# Peripherals.net
KiCad netlist of a schematic drawn in Altium Designer
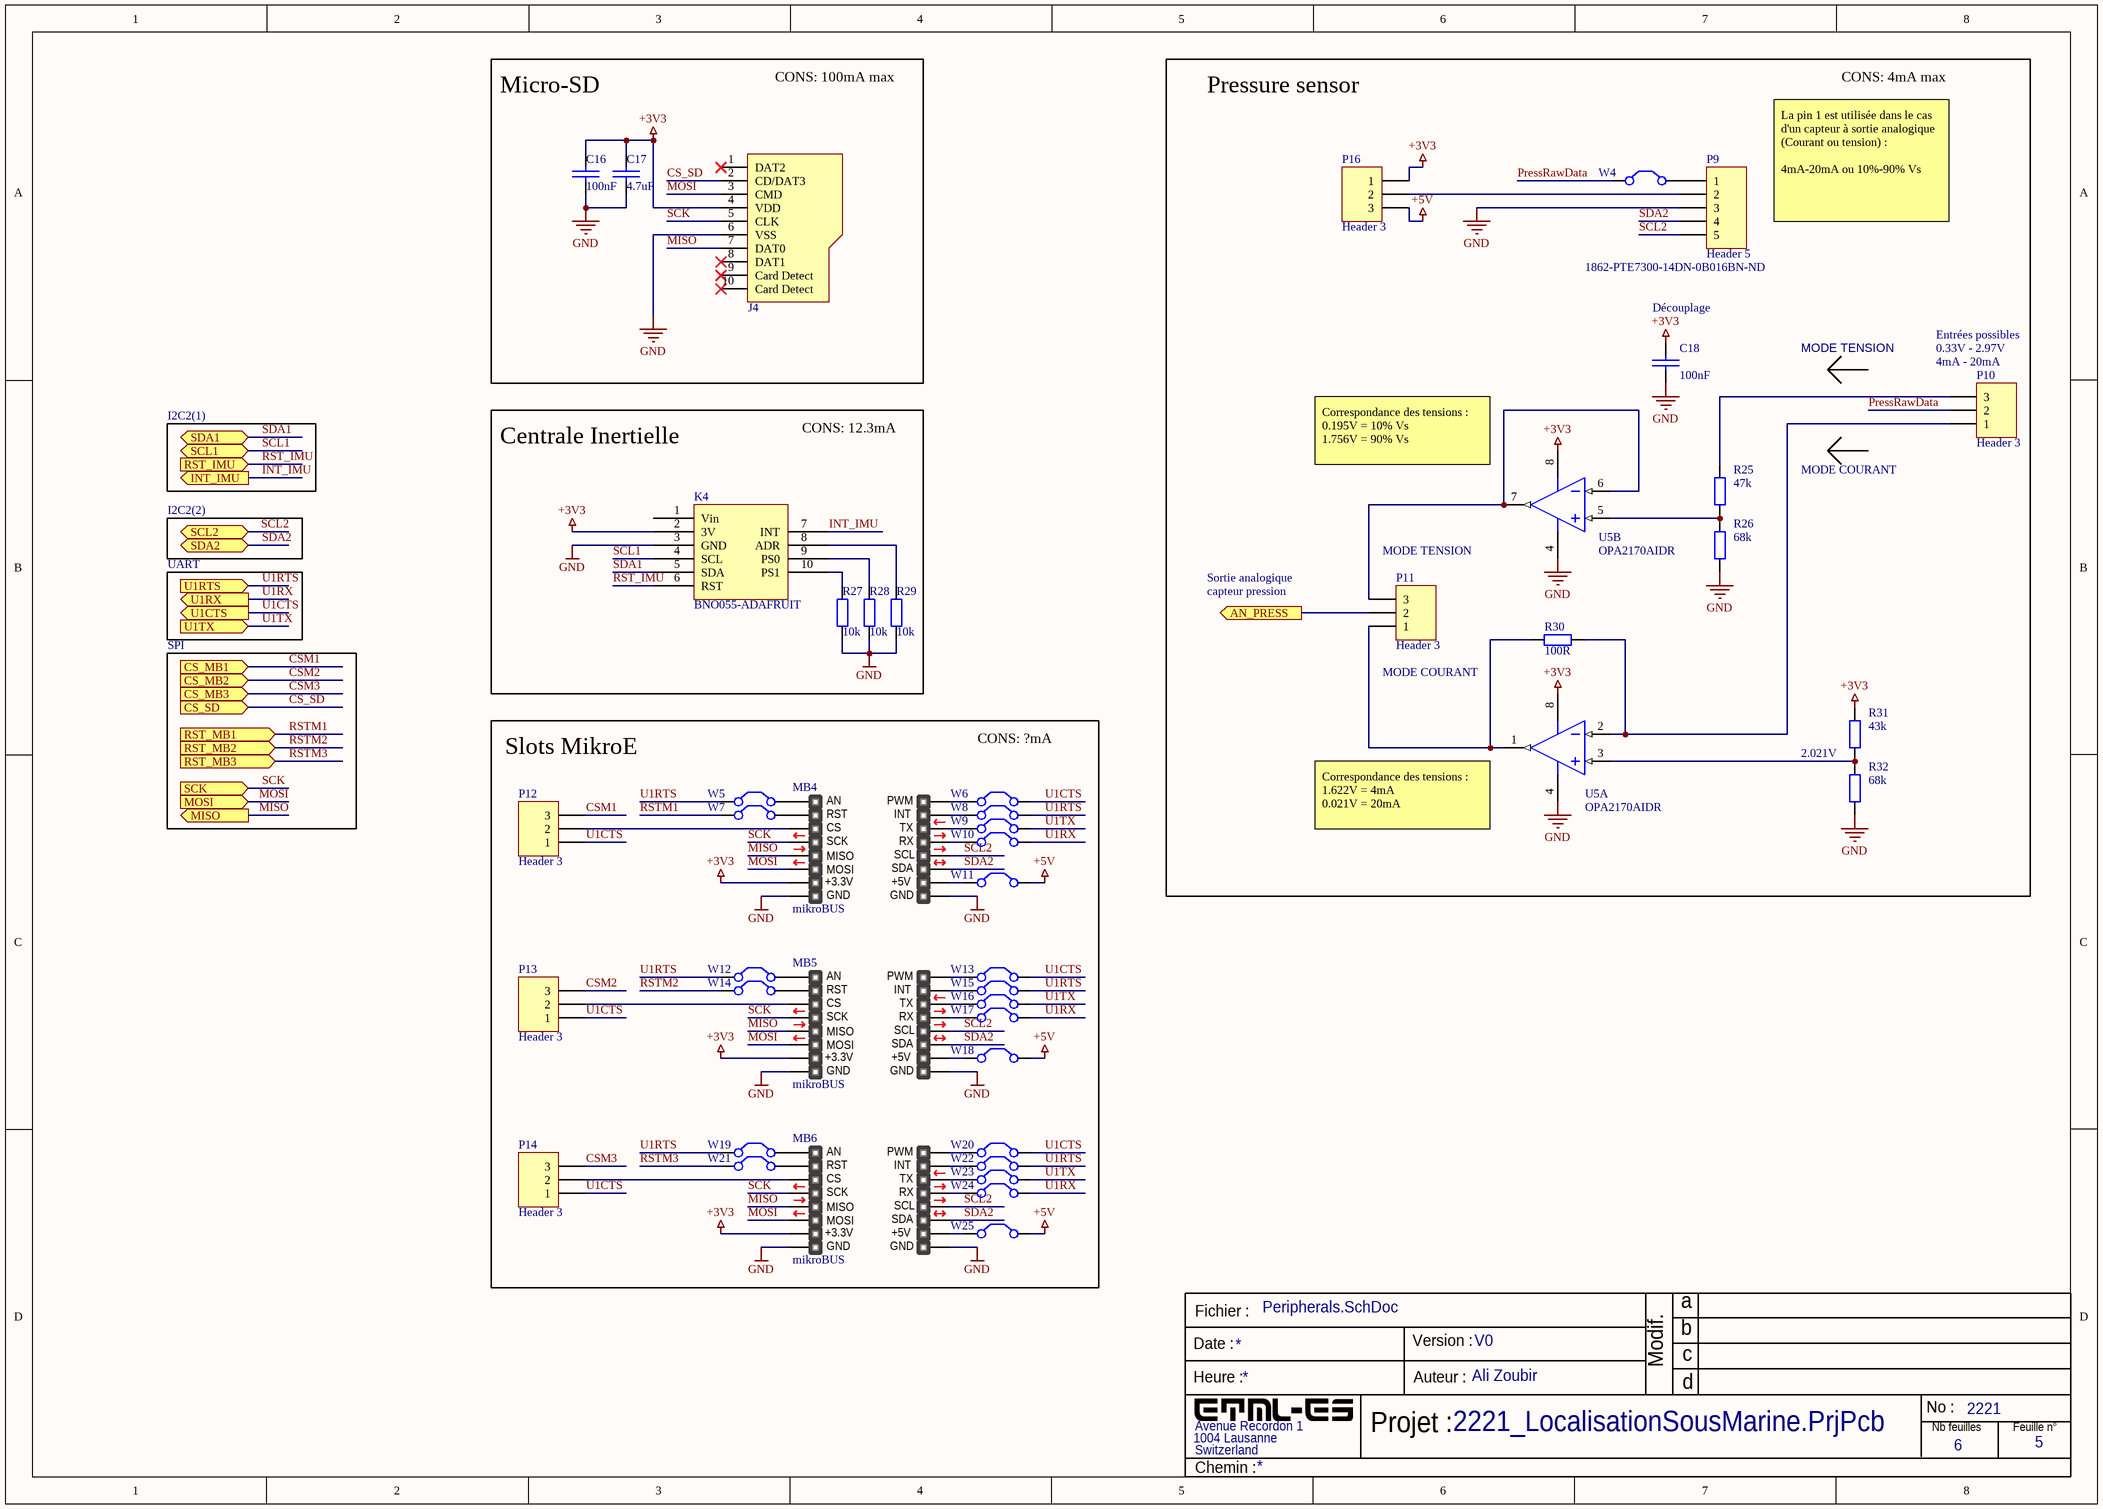
[diagram p0: Peripherals.SchDoc]

(export (version "E")
  (design (tool "Eeschema 10.0.6"))
  (components
    (comp (ref "C16") (value "100nF") (footprint "6-0805_L") (libsource (lib "*") (part "C")))
    (comp (ref "C17") (value "4.7uF") (footprint "6-0805_L") (libsource (lib "*") (part "C")))
    (comp (ref "C18") (value "100nF") (footprint "6-0805_L") (libsource (lib "*") (part "C")))
    (comp (ref "J4")
      (value "693071010811")
      (footprint "uSD-WE-693071010811")
      (description "WR-CRD Micro SD Card Connector Push & Push")
      (fields (field (name "MANUFACTURER") "Wurth Elektronik"))
      (libsource (lib "2221-LIB") (part "uSD-WE-693071010811"))
    )
    (comp (ref "K4")
      (value "BNO055-ADAFRUIT")
      (footprint "BNO055-ADAFRUIT")
      (libsource (lib "2221-LIB") (part "BNO055-ADAFRUIT"))
    )
    (comp (ref "MB4")
      (value "mikroBUS")
      (footprint "mikroBUS - Large")
      (description "mikroBUS compatible add-on board")
      (libsource (lib "mikroBUS_Add-on_standard") (part "mikroBUS compatible add-on board"))
    )
    (comp (ref "MB5")
      (value "mikroBUS")
      (footprint "mikroBUS - Large")
      (description "mikroBUS compatible add-on board")
      (libsource (lib "mikroBUS_Add-on_standard") (part "mikroBUS compatible add-on board"))
    )
    (comp (ref "MB6")
      (value "mikroBUS")
      (footprint "mikroBUS - Large")
      (description "mikroBUS compatible add-on board")
      (libsource (lib "mikroBUS_Add-on_standard") (part "mikroBUS compatible add-on board"))
    )
    (comp (ref "P9")
      (value "Header 5")
      (footprint "HDR1X5")
      (description "Header, 5-Pin")
      (fields
        (field (name "SUPPLIER PART NUMBER 1") "1862-PTE7300-14DN-0B016BN-ND")
        (field (name "PUBLISHER") "Altium Limited")
      )
      (libsource (lib "Miscellaneous Connectors") (part "Header 5"))
    )
    (comp (ref "P10")
      (value "Header 3")
      (footprint "HDR1X3")
      (description "Header, 3-Pin")
      (fields (field (name "PUBLISHER") "Altium Limited"))
      (libsource (lib "") (part "Header 3_2"))
    )
    (comp (ref "P11")
      (value "Header 3")
      (footprint "HDR1X3")
      (description "Header, 3-Pin")
      (fields (field (name "PUBLISHER") "Altium Limited"))
      (libsource (lib "") (part "Header 3_2"))
    )
    (comp (ref "P12")
      (value "Header 3")
      (footprint "HDR1X3")
      (description "Header, 3-Pin")
      (fields (field (name "PUBLISHER") "Altium Limited"))
      (libsource (lib "Miscellaneous Connectors") (part "Header 3"))
    )
    (comp (ref "P13")
      (value "Header 3")
      (footprint "HDR1X3")
      (description "Header, 3-Pin")
      (fields (field (name "PUBLISHER") "Altium Limited"))
      (libsource (lib "Miscellaneous Connectors") (part "Header 3"))
    )
    (comp (ref "P14")
      (value "Header 3")
      (footprint "HDR1X3")
      (description "Header, 3-Pin")
      (fields (field (name "PUBLISHER") "Altium Limited"))
      (libsource (lib "Miscellaneous Connectors") (part "Header 3"))
    )
    (comp (ref "P16")
      (value "Header 3")
      (footprint "HDR1X3")
      (description "Header, 3-Pin")
      (fields (field (name "PUBLISHER") "Altium Limited"))
      (libsource (lib "") (part "Header 3_1"))
    )
    (comp (ref "R25")
      (value "47k")
      (footprint "6-0805_L")
      (description "Res 0805")
      (fields (field (name "PUBLISHER") "Altium Limited"))
      (libsource (lib "Miscellaneous Devices") (part "Res2"))
    )
    (comp (ref "R26")
      (value "68k")
      (footprint "6-0805_L")
      (description "Res 0805")
      (fields (field (name "PUBLISHER") "Altium Limited"))
      (libsource (lib "Miscellaneous Devices") (part "Res2"))
    )
    (comp (ref "R27")
      (value "10k")
      (footprint "6-0805_L")
      (description "Res 0805")
      (fields (field (name "PUBLISHER") "Altium Limited"))
      (libsource (lib "Miscellaneous Devices") (part "Res2"))
    )
    (comp (ref "R28")
      (value "10k")
      (footprint "6-0805_L")
      (description "Res 0805")
      (fields (field (name "PUBLISHER") "Altium Limited"))
      (libsource (lib "Miscellaneous Devices") (part "Res2"))
    )
    (comp (ref "R29")
      (value "10k")
      (footprint "6-0805_L")
      (description "Res 0805")
      (fields (field (name "PUBLISHER") "Altium Limited"))
      (libsource (lib "Miscellaneous Devices") (part "Res2"))
    )
    (comp (ref "R30")
      (value "100R")
      (footprint "6-0805_L")
      (description "Res 0805")
      (fields (field (name "PUBLISHER") "Altium Limited"))
      (libsource (lib "") (part "Res2_1"))
    )
    (comp (ref "R31")
      (value "43k")
      (footprint "6-0805_L")
      (description "Res 0805")
      (fields (field (name "PUBLISHER") "Altium Limited"))
      (libsource (lib "Miscellaneous Devices") (part "Res2"))
    )
    (comp (ref "R32")
      (value "68k")
      (footprint "6-0805_L")
      (description "Res 0805")
      (fields (field (name "PUBLISHER") "Altium Limited"))
      (libsource (lib "Miscellaneous Devices") (part "Res2"))
    )
    (comp (ref "U5")
      (value "OPA2170AIDR")
      (footprint "D0008A_M")
      (fields (field (name "MANUFACTURER") "Texas Instruments"))
      (libsource (lib "Altium Content Vault") (part "TI-OPA-8_2"))
    )
    (comp (ref "W4")
      (value "Jumper")
      (footprint "JUMPER")
      (description "Jumper Wire")
      (fields (field (name "PUBLISHER") "Altium Limited"))
      (libsource (lib "Miscellaneous Devices") (part "Jumper"))
    )
    (comp (ref "W5")
      (value "Jumper")
      (footprint "JUMPER")
      (description "Jumper Wire")
      (fields (field (name "PUBLISHER") "Altium Limited"))
      (libsource (lib "Miscellaneous Devices") (part "Jumper"))
    )
    (comp (ref "W6")
      (value "Jumper")
      (footprint "JUMPER")
      (description "Jumper Wire")
      (fields (field (name "PUBLISHER") "Altium Limited"))
      (libsource (lib "Miscellaneous Devices") (part "Jumper"))
    )
    (comp (ref "W7")
      (value "Jumper")
      (footprint "JUMPER")
      (description "Jumper Wire")
      (fields (field (name "PUBLISHER") "Altium Limited"))
      (libsource (lib "Miscellaneous Devices") (part "Jumper"))
    )
    (comp (ref "W8")
      (value "Jumper")
      (footprint "JUMPER")
      (description "Jumper Wire")
      (fields (field (name "PUBLISHER") "Altium Limited"))
      (libsource (lib "Miscellaneous Devices") (part "Jumper"))
    )
    (comp (ref "W9")
      (value "Jumper")
      (footprint "JUMPER")
      (description "Jumper Wire")
      (fields (field (name "PUBLISHER") "Altium Limited"))
      (libsource (lib "Miscellaneous Devices") (part "Jumper"))
    )
    (comp (ref "W10")
      (value "Jumper")
      (footprint "JUMPER")
      (description "Jumper Wire")
      (fields (field (name "PUBLISHER") "Altium Limited"))
      (libsource (lib "Miscellaneous Devices") (part "Jumper"))
    )
    (comp (ref "W11")
      (value "Jumper")
      (footprint "JUMPER")
      (description "Jumper Wire")
      (fields (field (name "PUBLISHER") "Altium Limited"))
      (libsource (lib "Miscellaneous Devices") (part "Jumper"))
    )
    (comp (ref "W12")
      (value "Jumper")
      (footprint "JUMPER")
      (description "Jumper Wire")
      (fields (field (name "PUBLISHER") "Altium Limited"))
      (libsource (lib "Miscellaneous Devices") (part "Jumper"))
    )
    (comp (ref "W13")
      (value "Jumper")
      (footprint "JUMPER")
      (description "Jumper Wire")
      (fields (field (name "PUBLISHER") "Altium Limited"))
      (libsource (lib "Miscellaneous Devices") (part "Jumper"))
    )
    (comp (ref "W14")
      (value "Jumper")
      (footprint "JUMPER")
      (description "Jumper Wire")
      (fields (field (name "PUBLISHER") "Altium Limited"))
      (libsource (lib "Miscellaneous Devices") (part "Jumper"))
    )
    (comp (ref "W15")
      (value "Jumper")
      (footprint "JUMPER")
      (description "Jumper Wire")
      (fields (field (name "PUBLISHER") "Altium Limited"))
      (libsource (lib "Miscellaneous Devices") (part "Jumper"))
    )
    (comp (ref "W16")
      (value "Jumper")
      (footprint "JUMPER")
      (description "Jumper Wire")
      (fields (field (name "PUBLISHER") "Altium Limited"))
      (libsource (lib "Miscellaneous Devices") (part "Jumper"))
    )
    (comp (ref "W17")
      (value "Jumper")
      (footprint "JUMPER")
      (description "Jumper Wire")
      (fields (field (name "PUBLISHER") "Altium Limited"))
      (libsource (lib "Miscellaneous Devices") (part "Jumper"))
    )
    (comp (ref "W18")
      (value "Jumper")
      (footprint "JUMPER")
      (description "Jumper Wire")
      (fields (field (name "PUBLISHER") "Altium Limited"))
      (libsource (lib "Miscellaneous Devices") (part "Jumper"))
    )
    (comp (ref "W19")
      (value "Jumper")
      (footprint "JUMPER")
      (description "Jumper Wire")
      (fields (field (name "PUBLISHER") "Altium Limited"))
      (libsource (lib "Miscellaneous Devices") (part "Jumper"))
    )
    (comp (ref "W20")
      (value "Jumper")
      (footprint "JUMPER")
      (description "Jumper Wire")
      (fields (field (name "PUBLISHER") "Altium Limited"))
      (libsource (lib "Miscellaneous Devices") (part "Jumper"))
    )
    (comp (ref "W21")
      (value "Jumper")
      (footprint "JUMPER")
      (description "Jumper Wire")
      (fields (field (name "PUBLISHER") "Altium Limited"))
      (libsource (lib "Miscellaneous Devices") (part "Jumper"))
    )
    (comp (ref "W22")
      (value "Jumper")
      (footprint "JUMPER")
      (description "Jumper Wire")
      (fields (field (name "PUBLISHER") "Altium Limited"))
      (libsource (lib "Miscellaneous Devices") (part "Jumper"))
    )
    (comp (ref "W23")
      (value "Jumper")
      (footprint "JUMPER")
      (description "Jumper Wire")
      (fields (field (name "PUBLISHER") "Altium Limited"))
      (libsource (lib "Miscellaneous Devices") (part "Jumper"))
    )
    (comp (ref "W24")
      (value "Jumper")
      (footprint "JUMPER")
      (description "Jumper Wire")
      (fields (field (name "PUBLISHER") "Altium Limited"))
      (libsource (lib "Miscellaneous Devices") (part "Jumper"))
    )
    (comp (ref "W25")
      (value "Jumper")
      (footprint "JUMPER")
      (description "Jumper Wire")
      (fields (field (name "PUBLISHER") "Altium Limited"))
      (libsource (lib "Miscellaneous Devices") (part "Jumper"))
    )
  )
  (nets
    (net (code "1") (name "+3V3") (class "Default")
      (node (ref "C16") (pin "1") (pinfunction "1_1") (pintype "passive"))
      (node (ref "C17") (pin "1") (pinfunction "1_1") (pintype "passive"))
      (node (ref "C18") (pin "1") (pinfunction "1_1") (pintype "passive"))
      (node (ref "J4") (pin "4") (pinfunction "VDD_4") (pintype "passive"))
      (node (ref "K4") (pin "2") (pinfunction "3V_2") (pintype "passive"))
      (node (ref "MB4") (pin "7") (pinfunction "3.3V_7") (pintype "passive"))
      (node (ref "MB5") (pin "7") (pinfunction "3.3V_7") (pintype "passive"))
      (node (ref "MB6") (pin "7") (pinfunction "3.3V_7") (pintype "passive"))
      (node (ref "P16") (pin "1") (pinfunction "1_1") (pintype "passive"))
      (node (ref "R31") (pin "2") (pinfunction "2_2") (pintype "passive"))
      (node (ref "U5") (pin "8") (pinfunction "V+_8") (pintype "power_in"))
    )
    (net (code "2") (name "+5V") (class "Default")
      (node (ref "P16") (pin "3") (pinfunction "3_3") (pintype "passive"))
      (node (ref "W11") (pin "2") (pinfunction "C2_2") (pintype "passive"))
      (node (ref "W18") (pin "2") (pinfunction "C2_2") (pintype "passive"))
      (node (ref "W25") (pin "2") (pinfunction "C2_2") (pintype "passive"))
    )
    (net (code "3") (name "/AN_PRESS") (class "Default")
      (node (ref "P11") (pin "2") (pinfunction "2_2") (pintype "passive"))
    )
    (net (code "4") (name "/CSM1") (class "Default")
      (node (ref "P12") (pin "3") (pinfunction "3_3") (pintype "passive"))
    )
    (net (code "5") (name "/CSM2") (class "Default")
      (node (ref "P13") (pin "3") (pinfunction "3_3") (pintype "passive"))
    )
    (net (code "6") (name "/CSM3") (class "Default")
      (node (ref "P14") (pin "3") (pinfunction "3_3") (pintype "passive"))
    )
    (net (code "7") (name "/CS_SD") (class "Default")
      (node (ref "J4") (pin "2") (pinfunction "CD/DAT3_2") (pintype "passive"))
    )
    (net (code "8") (name "/INT_IMU") (class "Default")
      (node (ref "K4") (pin "7") (pinfunction "INT_7") (pintype "passive"))
    )
    (net (code "9") (name "/MISO") (class "Default")
      (node (ref "J4") (pin "7") (pinfunction "DAT0_7") (pintype "passive"))
      (node (ref "MB4") (pin "5") (pinfunction "MISO_5") (pintype "passive"))
      (node (ref "MB5") (pin "5") (pinfunction "MISO_5") (pintype "passive"))
      (node (ref "MB6") (pin "5") (pinfunction "MISO_5") (pintype "passive"))
    )
    (net (code "10") (name "/MOSI") (class "Default")
      (node (ref "J4") (pin "3") (pinfunction "CMD_3") (pintype "passive"))
      (node (ref "MB4") (pin "6") (pinfunction "MOSI_6") (pintype "passive"))
      (node (ref "MB5") (pin "6") (pinfunction "MOSI_6") (pintype "passive"))
      (node (ref "MB6") (pin "6") (pinfunction "MOSI_6") (pintype "passive"))
    )
    (net (code "11") (name "/PressRawData") (class "Default")
      (node (ref "P10") (pin "2") (pinfunction "2_2") (pintype "passive"))
      (node (ref "W4") (pin "1") (pinfunction "C1_1") (pintype "passive"))
    )
    (net (code "12") (name "/RSTM1") (class "Default")
      (node (ref "W7") (pin "1") (pinfunction "C1_1") (pintype "passive"))
    )
    (net (code "13") (name "/RSTM2") (class "Default")
      (node (ref "W14") (pin "1") (pinfunction "C1_1") (pintype "passive"))
    )
    (net (code "14") (name "/RSTM3") (class "Default")
      (node (ref "W21") (pin "1") (pinfunction "C1_1") (pintype "passive"))
    )
    (net (code "15") (name "/RST_IMU") (class "Default")
      (node (ref "K4") (pin "6") (pinfunction "RST_6") (pintype "passive"))
    )
    (net (code "16") (name "/SCK") (class "Default")
      (node (ref "J4") (pin "5") (pinfunction "CLK_5") (pintype "passive"))
      (node (ref "MB4") (pin "4") (pinfunction "SCK_4") (pintype "passive"))
      (node (ref "MB5") (pin "4") (pinfunction "SCK_4") (pintype "passive"))
      (node (ref "MB6") (pin "4") (pinfunction "SCK_4") (pintype "passive"))
    )
    (net (code "17") (name "/SCL1") (class "Default")
      (node (ref "K4") (pin "4") (pinfunction "SCL_4") (pintype "passive"))
    )
    (net (code "18") (name "/SCL2") (class "Default")
      (node (ref "MB4") (pin "12") (pinfunction "SCL_12") (pintype "passive"))
      (node (ref "MB5") (pin "12") (pinfunction "SCL_12") (pintype "passive"))
      (node (ref "MB6") (pin "12") (pinfunction "SCL_12") (pintype "passive"))
      (node (ref "P9") (pin "5") (pinfunction "5_5") (pintype "passive"))
    )
    (net (code "19") (name "/SDA1") (class "Default")
      (node (ref "K4") (pin "5") (pinfunction "SDA_5") (pintype "passive"))
    )
    (net (code "20") (name "/SDA2") (class "Default")
      (node (ref "MB4") (pin "11") (pinfunction "SDA_11") (pintype "passive"))
      (node (ref "MB5") (pin "11") (pinfunction "SDA_11") (pintype "passive"))
      (node (ref "MB6") (pin "11") (pinfunction "SDA_11") (pintype "passive"))
      (node (ref "P9") (pin "4") (pinfunction "4_4") (pintype "passive"))
    )
    (net (code "21") (name "/U1CTS") (class "Default")
      (node (ref "P12") (pin "1") (pinfunction "1_1") (pintype "passive"))
      (node (ref "P13") (pin "1") (pinfunction "1_1") (pintype "passive"))
      (node (ref "P14") (pin "1") (pinfunction "1_1") (pintype "passive"))
      (node (ref "W13") (pin "2") (pinfunction "C2_2") (pintype "passive"))
      (node (ref "W20") (pin "2") (pinfunction "C2_2") (pintype "passive"))
      (node (ref "W6") (pin "2") (pinfunction "C2_2") (pintype "passive"))
    )
    (net (code "22") (name "/U1RTS") (class "Default")
      (node (ref "W12") (pin "1") (pinfunction "C1_1") (pintype "passive"))
      (node (ref "W15") (pin "2") (pinfunction "C2_2") (pintype "passive"))
      (node (ref "W19") (pin "1") (pinfunction "C1_1") (pintype "passive"))
      (node (ref "W22") (pin "2") (pinfunction "C2_2") (pintype "passive"))
      (node (ref "W5") (pin "1") (pinfunction "C1_1") (pintype "passive"))
      (node (ref "W8") (pin "2") (pinfunction "C2_2") (pintype "passive"))
    )
    (net (code "23") (name "/U1RX") (class "Default")
      (node (ref "W10") (pin "2") (pinfunction "C2_2") (pintype "passive"))
      (node (ref "W17") (pin "2") (pinfunction "C2_2") (pintype "passive"))
      (node (ref "W24") (pin "2") (pinfunction "C2_2") (pintype "passive"))
    )
    (net (code "24") (name "/U1TX") (class "Default")
      (node (ref "W16") (pin "2") (pinfunction "C2_2") (pintype "passive"))
      (node (ref "W23") (pin "2") (pinfunction "C2_2") (pintype "passive"))
      (node (ref "W9") (pin "2") (pinfunction "C2_2") (pintype "passive"))
    )
    (net (code "25") (name "GND") (class "Default")
      (node (ref "C16") (pin "2") (pinfunction "2_2") (pintype "passive"))
      (node (ref "C17") (pin "2") (pinfunction "2_2") (pintype "passive"))
      (node (ref "C18") (pin "2") (pinfunction "2_2") (pintype "passive"))
      (node (ref "J4") (pin "6") (pinfunction "VSS_6") (pintype "passive"))
      (node (ref "K4") (pin "3") (pinfunction "GND_3") (pintype "passive"))
      (node (ref "MB4") (pin "8") (pinfunction "GND_8") (pintype "passive"))
      (node (ref "MB4") (pin "9") (pinfunction "GND_9") (pintype "passive"))
      (node (ref "MB5") (pin "8") (pinfunction "GND_8") (pintype "passive"))
      (node (ref "MB5") (pin "9") (pinfunction "GND_9") (pintype "passive"))
      (node (ref "MB6") (pin "8") (pinfunction "GND_8") (pintype "passive"))
      (node (ref "MB6") (pin "9") (pinfunction "GND_9") (pintype "passive"))
      (node (ref "P9") (pin "3") (pinfunction "3_3") (pintype "passive"))
      (node (ref "R26") (pin "1") (pinfunction "1_1") (pintype "passive"))
      (node (ref "R27") (pin "1") (pinfunction "1_1") (pintype "passive"))
      (node (ref "R28") (pin "1") (pinfunction "1_1") (pintype "passive"))
      (node (ref "R29") (pin "1") (pinfunction "1_1") (pintype "passive"))
      (node (ref "R32") (pin "1") (pinfunction "1_1") (pintype "passive"))
      (node (ref "U5") (pin "4") (pinfunction "V-_4") (pintype "power_in"))
    )
    (net (code "26") (name "Net-(K4-ADR)") (class "Default")
      (node (ref "K4") (pin "8") (pinfunction "ADR_8") (pintype "passive"))
      (node (ref "R29") (pin "2") (pinfunction "2_2") (pintype "passive"))
    )
    (net (code "27") (name "Net-(K4-PS0)") (class "Default")
      (node (ref "K4") (pin "9") (pinfunction "PS0_9") (pintype "passive"))
      (node (ref "R28") (pin "2") (pinfunction "2_2") (pintype "passive"))
    )
    (net (code "28") (name "Net-(K4-PS1)") (class "Default")
      (node (ref "K4") (pin "10") (pinfunction "PS1_10") (pintype "passive"))
      (node (ref "R27") (pin "2") (pinfunction "2_2") (pintype "passive"))
    )
    (net (code "29") (name "Net-(MB4-5V)") (class "Default")
      (node (ref "MB4") (pin "10") (pinfunction "5V_10") (pintype "passive"))
      (node (ref "W11") (pin "1") (pinfunction "C1_1") (pintype "passive"))
    )
    (net (code "30") (name "Net-(MB4-AN)") (class "Default")
      (node (ref "MB4") (pin "1") (pinfunction "AN_1") (pintype "passive"))
      (node (ref "W5") (pin "2") (pinfunction "C2_2") (pintype "passive"))
    )
    (net (code "31") (name "Net-(MB4-CS)") (class "Default")
      (node (ref "MB4") (pin "3") (pinfunction "CS_3") (pintype "passive"))
      (node (ref "P12") (pin "2") (pinfunction "2_2") (pintype "passive"))
    )
    (net (code "32") (name "Net-(MB4-INT)") (class "Default")
      (node (ref "MB4") (pin "15") (pinfunction "INT_15") (pintype "passive"))
      (node (ref "W8") (pin "1") (pinfunction "C1_1") (pintype "passive"))
    )
    (net (code "33") (name "Net-(MB4-PWM)") (class "Default")
      (node (ref "MB4") (pin "16") (pinfunction "PWM_16") (pintype "passive"))
      (node (ref "W6") (pin "1") (pinfunction "C1_1") (pintype "passive"))
    )
    (net (code "34") (name "Net-(MB4-RST)") (class "Default")
      (node (ref "MB4") (pin "2") (pinfunction "RST_2") (pintype "passive"))
      (node (ref "W7") (pin "2") (pinfunction "C2_2") (pintype "passive"))
    )
    (net (code "35") (name "Net-(MB4-RX)") (class "Default")
      (node (ref "MB4") (pin "14") (pinfunction "RX_14") (pintype "passive"))
      (node (ref "W9") (pin "1") (pinfunction "C1_1") (pintype "passive"))
    )
    (net (code "36") (name "Net-(MB4-TX)") (class "Default")
      (node (ref "MB4") (pin "13") (pinfunction "TX_13") (pintype "passive"))
      (node (ref "W10") (pin "1") (pinfunction "C1_1") (pintype "passive"))
    )
    (net (code "37") (name "Net-(MB5-5V)") (class "Default")
      (node (ref "MB5") (pin "10") (pinfunction "5V_10") (pintype "passive"))
      (node (ref "W18") (pin "1") (pinfunction "C1_1") (pintype "passive"))
    )
    (net (code "38") (name "Net-(MB5-AN)") (class "Default")
      (node (ref "MB5") (pin "1") (pinfunction "AN_1") (pintype "passive"))
      (node (ref "W12") (pin "2") (pinfunction "C2_2") (pintype "passive"))
    )
    (net (code "39") (name "Net-(MB5-CS)") (class "Default")
      (node (ref "MB5") (pin "3") (pinfunction "CS_3") (pintype "passive"))
      (node (ref "P13") (pin "2") (pinfunction "2_2") (pintype "passive"))
    )
    (net (code "40") (name "Net-(MB5-INT)") (class "Default")
      (node (ref "MB5") (pin "15") (pinfunction "INT_15") (pintype "passive"))
      (node (ref "W15") (pin "1") (pinfunction "C1_1") (pintype "passive"))
    )
    (net (code "41") (name "Net-(MB5-PWM)") (class "Default")
      (node (ref "MB5") (pin "16") (pinfunction "PWM_16") (pintype "passive"))
      (node (ref "W13") (pin "1") (pinfunction "C1_1") (pintype "passive"))
    )
    (net (code "42") (name "Net-(MB5-RST)") (class "Default")
      (node (ref "MB5") (pin "2") (pinfunction "RST_2") (pintype "passive"))
      (node (ref "W14") (pin "2") (pinfunction "C2_2") (pintype "passive"))
    )
    (net (code "43") (name "Net-(MB5-RX)") (class "Default")
      (node (ref "MB5") (pin "14") (pinfunction "RX_14") (pintype "passive"))
      (node (ref "W16") (pin "1") (pinfunction "C1_1") (pintype "passive"))
    )
    (net (code "44") (name "Net-(MB5-TX)") (class "Default")
      (node (ref "MB5") (pin "13") (pinfunction "TX_13") (pintype "passive"))
      (node (ref "W17") (pin "1") (pinfunction "C1_1") (pintype "passive"))
    )
    (net (code "45") (name "Net-(MB6-5V)") (class "Default")
      (node (ref "MB6") (pin "10") (pinfunction "5V_10") (pintype "passive"))
      (node (ref "W25") (pin "1") (pinfunction "C1_1") (pintype "passive"))
    )
    (net (code "46") (name "Net-(MB6-AN)") (class "Default")
      (node (ref "MB6") (pin "1") (pinfunction "AN_1") (pintype "passive"))
      (node (ref "W19") (pin "2") (pinfunction "C2_2") (pintype "passive"))
    )
    (net (code "47") (name "Net-(MB6-CS)") (class "Default")
      (node (ref "MB6") (pin "3") (pinfunction "CS_3") (pintype "passive"))
      (node (ref "P14") (pin "2") (pinfunction "2_2") (pintype "passive"))
    )
    (net (code "48") (name "Net-(MB6-INT)") (class "Default")
      (node (ref "MB6") (pin "15") (pinfunction "INT_15") (pintype "passive"))
      (node (ref "W22") (pin "1") (pinfunction "C1_1") (pintype "passive"))
    )
    (net (code "49") (name "Net-(MB6-PWM)") (class "Default")
      (node (ref "MB6") (pin "16") (pinfunction "PWM_16") (pintype "passive"))
      (node (ref "W20") (pin "1") (pinfunction "C1_1") (pintype "passive"))
    )
    (net (code "50") (name "Net-(MB6-RST)") (class "Default")
      (node (ref "MB6") (pin "2") (pinfunction "RST_2") (pintype "passive"))
      (node (ref "W21") (pin "2") (pinfunction "C2_2") (pintype "passive"))
    )
    (net (code "51") (name "Net-(MB6-RX)") (class "Default")
      (node (ref "MB6") (pin "14") (pinfunction "RX_14") (pintype "passive"))
      (node (ref "W23") (pin "1") (pinfunction "C1_1") (pintype "passive"))
    )
    (net (code "52") (name "Net-(MB6-TX)") (class "Default")
      (node (ref "MB6") (pin "13") (pinfunction "TX_13") (pintype "passive"))
      (node (ref "W24") (pin "1") (pinfunction "C1_1") (pintype "passive"))
    )
    (net (code "53") (name "Net-(P10-Pad3)") (class "Default")
      (node (ref "P10") (pin "3") (pinfunction "3_3") (pintype "passive"))
      (node (ref "R25") (pin "2") (pinfunction "2_2") (pintype "passive"))
    )
    (net (code "54") (name "Net-(P16-Pad2)") (class "Default")
      (node (ref "P16") (pin "2") (pinfunction "2_2") (pintype "passive"))
      (node (ref "P9") (pin "2") (pinfunction "2_2") (pintype "passive"))
    )
    (net (code "55") (name "Net-(U5A-IN_A+)") (class "Default")
      (node (ref "R31") (pin "1") (pinfunction "1_1") (pintype "passive"))
      (node (ref "R32") (pin "2") (pinfunction "2_2") (pintype "passive"))
      (node (ref "U5") (pin "3") (pinfunction "IN_A+_3") (pintype "input"))
    )
    (net (code "56") (name "Net-(U5A-IN_A-)") (class "Default")
      (node (ref "P10") (pin "1") (pinfunction "1_1") (pintype "passive"))
      (node (ref "R30") (pin "1") (pinfunction "1_1") (pintype "passive"))
      (node (ref "U5") (pin "2") (pinfunction "IN_A-_2") (pintype "input"))
    )
    (net (code "57") (name "Net-(U5A-OUT_A)") (class "Default")
      (node (ref "P11") (pin "1") (pinfunction "1_1") (pintype "passive"))
      (node (ref "R30") (pin "2") (pinfunction "2_2") (pintype "passive"))
      (node (ref "U5") (pin "1") (pinfunction "OUT_A_1") (pintype "output"))
    )
    (net (code "58") (name "Net-(U5B-IN_B+)") (class "Default")
      (node (ref "R25") (pin "1") (pinfunction "1_1") (pintype "passive"))
      (node (ref "R26") (pin "2") (pinfunction "2_2") (pintype "passive"))
      (node (ref "U5") (pin "5") (pinfunction "IN_B+_5") (pintype "input"))
    )
    (net (code "59") (name "Net-(U5B-IN_B-)") (class "Default")
      (node (ref "P11") (pin "3") (pinfunction "3_3") (pintype "passive"))
      (node (ref "U5") (pin "6") (pinfunction "IN_B-_6") (pintype "input"))
      (node (ref "U5") (pin "7") (pinfunction "OUT_B_7") (pintype "output"))
    )
    (net (code "60") (name "Net-(W4-C2)") (class "Default")
      (node (ref "P9") (pin "1") (pinfunction "1_1") (pintype "passive"))
      (node (ref "W4") (pin "2") (pinfunction "C2_2") (pintype "passive"))
    )
    (net (code "61") (name "unconnected-(J4-Card_Detect-Pad9)") (class "Default")
      (node (ref "J4") (pin "9") (pinfunction "Card_Detect_9") (pintype "passive+no_connect"))
    )
    (net (code "62") (name "unconnected-(J4-Card_Detect-Pad10)") (class "Default")
      (node (ref "J4") (pin "10") (pinfunction "Card_Detect_10") (pintype "passive+no_connect"))
    )
    (net (code "63") (name "unconnected-(J4-DAT1-Pad8)") (class "Default")
      (node (ref "J4") (pin "8") (pinfunction "DAT1_8") (pintype "passive+no_connect"))
    )
    (net (code "64") (name "unconnected-(J4-DAT2-Pad1)") (class "Default")
      (node (ref "J4") (pin "1") (pinfunction "DAT2_1") (pintype "passive+no_connect"))
    )
    (net (code "65") (name "unconnected-(K4-Vin-Pad1)") (class "Default")
      (node (ref "K4") (pin "1") (pinfunction "Vin_1") (pintype "passive"))
    )
  )
)
